# Sheet2_Power.net
KiCad netlist of a schematic drawn in Altium Designer
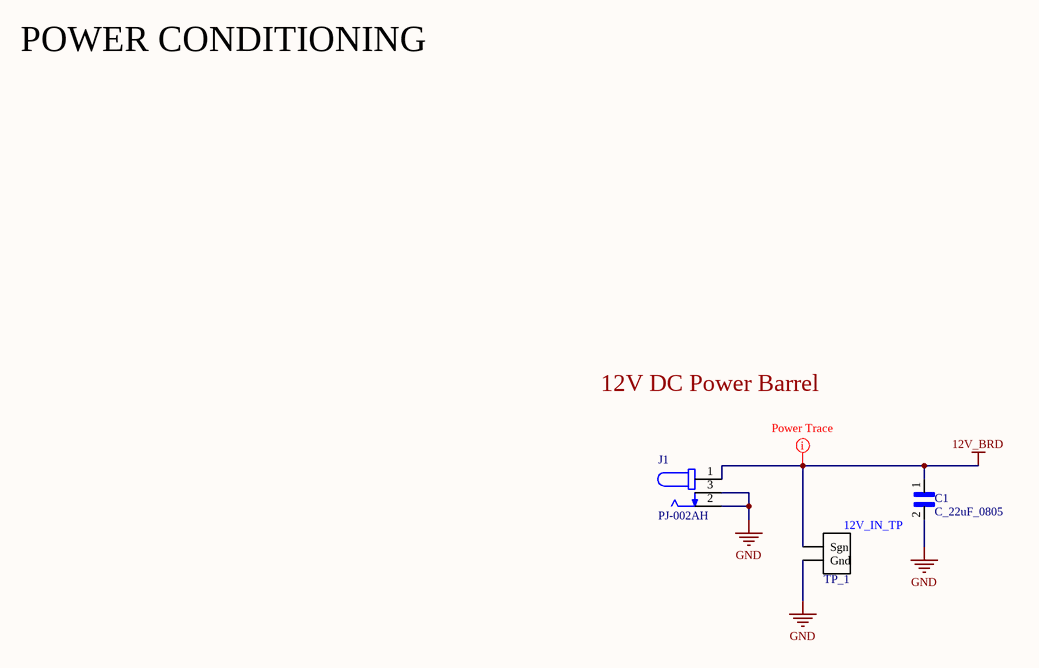
[diagram p0: Sheet2_Power.SchDoc]

(export (version "E")
  (design (tool "Eeschema 10.0.6"))
  (components
    (comp (ref "C1")
      (value "C_22uF_0805")
      (footprint "CAPC2012X140N")
      (description "22µF 0805 ±20% 25V Ceramic Capacitor X5R 0805 (2012 Metric)")
      (fields (field (name "MF") "Samsung") (field (name "DIGI-KEY_PART_NUMBER") "1276-2908-1-ND"))
      (libsource (lib "Homie_IntegratedLibraryV2") (part "C_22uF_0805"))
    )
    (comp (ref "J1")
      (value "PJ-002AH")
      (footprint "CUI_PJ-002AH")
      (description "2.0 x 6.5 mm, 5.0 A, Horizontal, Through Hole, Dc Power Jack Connector")
      (fields (field (name "DIGI-KEY_PART_NUMBER") "CP-002AH-ND") (field (name "MF") "CUI Devices"))
      (libsource (lib "Homie_IntegratedLibraryV3") (part "PJ-002AH"))
    )
    (comp (ref "TP_1")
      (value "10x Probe TP")
      (footprint "TP10x_Probe")
      (description "Test Point 300 mil centers")
      (libsource (lib "ECEN5730Lib_2020_09_AR") (part "TP_10x_Probe"))
    )
  )
  (nets
    (net (code "1") (name "12V_BRD") (class "Default")
      (node (ref "C1") (pin "1") (pinfunction "1_1") (pintype "passive"))
      (node (ref "J1") (pin "1") (pinfunction "1_1") (pintype "passive"))
      (node (ref "TP_1") (pin "1") (pinfunction "Sgn_1") (pintype "passive"))
    )
    (net (code "2") (name "GND") (class "Default")
      (node (ref "C1") (pin "2") (pinfunction "2_2") (pintype "passive"))
      (node (ref "J1") (pin "2") (pinfunction "2_2") (pintype "passive"))
      (node (ref "J1") (pin "3") (pinfunction "3_3") (pintype "passive"))
      (node (ref "TP_1") (pin "2") (pinfunction "Gnd_2") (pintype "passive"))
    )
  )
)
